# cs301_Group2_Sensing.net
KiCad netlist of a schematic drawn in Altium Designer
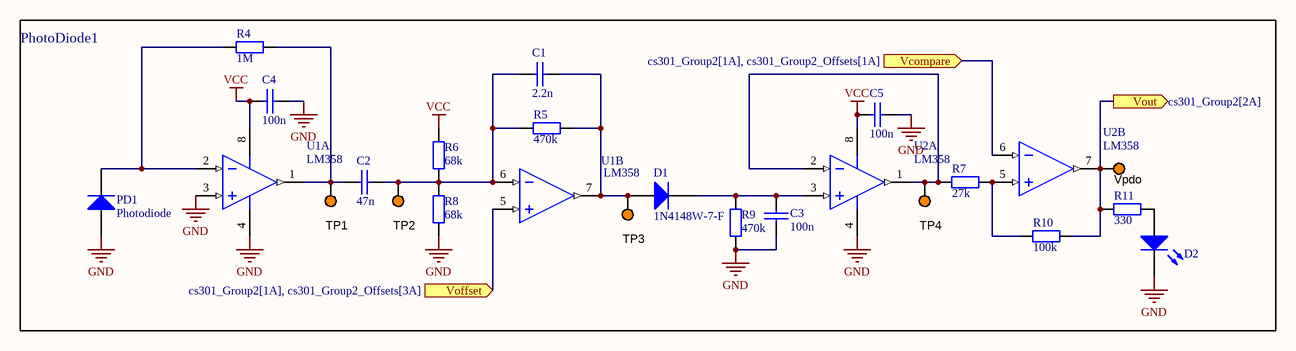
[diagram p0: cs301_Group2_Sensing.SchDoc]

(export (version "E")
  (design (tool "Eeschema 10.0.6"))
  (components
    (comp (ref "C1")
      (value "2.2n")
      (footprint "0805 CAP")
      (description "SMT ceramic capacitor 0805 size")
      (libsource (lib "EE209_Library") (part "CerCap_SMT_0805"))
    )
    (comp (ref "C2")
      (value "47n")
      (footprint "0805 CAP")
      (description "SMT ceramic capacitor 0805 size")
      (libsource (lib "EE209_Library") (part "CerCap_SMT_0805"))
    )
    (comp (ref "C3")
      (value "100n")
      (footprint "0805 CAP")
      (description "SMT ceramic capacitor 0805 size")
      (libsource (lib "EE209_Library") (part "CerCap_SMT_0805"))
    )
    (comp (ref "C4")
      (value "100n")
      (footprint "0805 CAP")
      (description "SMT ceramic capacitor 0805 size")
      (libsource (lib "EE209_Library") (part "CerCap_SMT_0805"))
    )
    (comp (ref "C5")
      (value "100n")
      (footprint "0805 CAP")
      (description "SMT ceramic capacitor 0805 size")
      (libsource (lib "EE209_Library") (part "CerCap_SMT_0805"))
    )
    (comp (ref "D1")
      (value "1N4148W-7-F")
      (footprint "SOD123")
      (description "1N4148 100V 200mA SOD-123 diode")
      (fields
        (field (name "MANUFACTURER") "ON Semiconductor")
        (field (name "MANUFACTURER PART NUMBER") "1N4148TR")
      )
      (libsource (lib "EE209_Library") (part "ES1H_SMT_DO214"))
    )
    (comp (ref "D2")
      (value "LTST-C170KGKT")
      (footprint "0805 LED")
      (description "SMT LED 0805 size")
      (fields (field (name "MANUFACTURER") "Lite-On Inc."))
      (libsource (lib "EE209_Library") (part "LED_SMT_0805"))
    )
    (comp (ref "PD1")
      (value "Photodiode")
      (footprint "SOD123")
      (description "DIODE GEN PURP 100V 300MA SOD123")
      (fields
        (field (name "MANUFACTURER") "Diodes Incorporated")
        (field (name "MANUFACTURER PART NUMBER") "1N4148W-13-F")
      )
      (libsource (lib "EE209_Library") (part "1N4148_SMT_SOD123"))
    )
    (comp (ref "R4")
      (value "1M")
      (footprint "0805 RES")
      (description "0805 resistor")
      (fields (field (name "PUBLISHER") "Altium Limited"))
      (libsource (lib "") (part "Res_SMT_0805_1"))
    )
    (comp (ref "R5")
      (value "470k")
      (footprint "0805 RES")
      (description "0805 resistor")
      (fields (field (name "PUBLISHER") "Altium Limited"))
      (libsource (lib "") (part "Res_SMT_0805_1"))
    )
    (comp (ref "R6")
      (value "68k")
      (footprint "0805 RES")
      (description "0805 resistor")
      (fields (field (name "PUBLISHER") "Altium Limited"))
      (libsource (lib "EE209_Library") (part "Res_SMT_0805"))
    )
    (comp (ref "R7")
      (value "27k")
      (footprint "0805 RES")
      (description "0805 resistor")
      (fields (field (name "PUBLISHER") "Altium Limited"))
      (libsource (lib "") (part "Res_SMT_0805_1"))
    )
    (comp (ref "R8")
      (value "68k")
      (footprint "0805 RES")
      (description "0805 resistor")
      (fields (field (name "PUBLISHER") "Altium Limited"))
      (libsource (lib "EE209_Library") (part "Res_SMT_0805"))
    )
    (comp (ref "R9")
      (value "470k")
      (footprint "0805 RES")
      (description "0805 resistor")
      (fields (field (name "PUBLISHER") "Altium Limited"))
      (libsource (lib "EE209_Library") (part "Res_SMT_0805"))
    )
    (comp (ref "R10")
      (value "100k")
      (footprint "0805 RES")
      (description "0805 resistor")
      (fields (field (name "PUBLISHER") "Altium Limited"))
      (libsource (lib "") (part "Res_SMT_0805_1"))
    )
    (comp (ref "R11")
      (value "330")
      (footprint "0805 RES")
      (description "0805 resistor")
      (fields (field (name "PUBLISHER") "Altium Limited"))
      (libsource (lib "") (part "Res_SMT_0805_2"))
    )
    (comp (ref "TP1")
      (value "5003")
      (footprint "TP_TH")
      (description "Test Point, Orange, 1-Pin THD, RoHS")
      (libsource (lib "EE209_Library") (part "TestPoint"))
    )
    (comp (ref "TP2")
      (value "5003")
      (footprint "TP_TH")
      (description "Test Point, Orange, 1-Pin THD, RoHS")
      (libsource (lib "EE209_Library") (part "TestPoint"))
    )
    (comp (ref "TP3")
      (value "5003")
      (footprint "TP_TH")
      (description "Test Point, Orange, 1-Pin THD, RoHS")
      (libsource (lib "EE209_Library") (part "TestPoint"))
    )
    (comp (ref "TP4")
      (value "5003")
      (footprint "TP_TH")
      (description "Test Point, Orange, 1-Pin THD, RoHS")
      (libsource (lib "EE209_Library") (part "TestPoint"))
    )
    (comp (ref "U1")
      (value "LM358")
      (footprint "SO - 8")
      (description "IC OPAMP 8SOIC")
      (libsource (lib "EE209_Library") (part "LM358_SMT_SOIC8"))
    )
    (comp (ref "U2")
      (value "LM358")
      (footprint "SO - 8")
      (description "IC OPAMP 8SOIC")
      (libsource (lib "EE209_Library") (part "LM358_SMT_SOIC8"))
    )
    (comp (ref "Vpdo")
      (value "5003")
      (footprint "TP_TH")
      (description "Test Point, Orange, 1-Pin THD, RoHS")
      (libsource (lib "EE209_Library") (part "TestPoint"))
    )
  )
  (nets
    (net (code "1") (name "/Vcompare") (class "Default")
      (node (ref "U2") (pin "6") (pinfunction "VINA-_6") (pintype "input"))
    )
    (net (code "2") (name "/Voffset") (class "Default")
      (node (ref "U1") (pin "5") (pinfunction "VINA+_5") (pintype "input"))
    )
    (net (code "3") (name "/Vout") (class "Default")
      (node (ref "R10") (pin "1") (pinfunction "1_1") (pintype "passive"))
      (node (ref "R11") (pin "1") (pinfunction "1_1") (pintype "passive"))
      (node (ref "U2") (pin "7") (pinfunction "VOUTA_7") (pintype "output"))
      (node (ref "Vpdo") (pin "1") (pinfunction "1_1") (pintype "passive"))
    )
    (net (code "4") (name "GND") (class "Default")
      (node (ref "C3") (pin "1") (pinfunction "1_1") (pintype "passive"))
      (node (ref "C4") (pin "2") (pinfunction "2_2") (pintype "passive"))
      (node (ref "C5") (pin "2") (pinfunction "2_2") (pintype "passive"))
      (node (ref "D2") (pin "2") (pinfunction "K_2") (pintype "passive"))
      (node (ref "PD1") (pin "1") (pinfunction "A_1") (pintype "passive"))
      (node (ref "R8") (pin "1") (pinfunction "1_1") (pintype "passive"))
      (node (ref "R9") (pin "1") (pinfunction "1_1") (pintype "passive"))
      (node (ref "U1") (pin "3") (pinfunction "VINA+_3") (pintype "input"))
      (node (ref "U1") (pin "4") (pinfunction "VSS_4") (pintype "power_in"))
      (node (ref "U2") (pin "4") (pinfunction "VSS_4") (pintype "power_in"))
    )
    (net (code "5") (name "Net-(D1-A)") (class "Default")
      (node (ref "C1") (pin "2") (pinfunction "2_2") (pintype "passive"))
      (node (ref "D1") (pin "1") (pinfunction "A_1") (pintype "passive"))
      (node (ref "R5") (pin "1") (pinfunction "1_1") (pintype "passive"))
      (node (ref "TP3") (pin "1") (pinfunction "1_1") (pintype "passive"))
      (node (ref "U1") (pin "7") (pinfunction "VOUTA_7") (pintype "output"))
    )
    (net (code "6") (name "Net-(D1-K)") (class "Default")
      (node (ref "C3") (pin "2") (pinfunction "2_2") (pintype "passive"))
      (node (ref "D1") (pin "2") (pinfunction "K_2") (pintype "passive"))
      (node (ref "R9") (pin "2") (pinfunction "2_2") (pintype "passive"))
      (node (ref "U2") (pin "3") (pinfunction "VINA+_3") (pintype "input"))
    )
    (net (code "7") (name "Net-(D2-A)") (class "Default")
      (node (ref "D2") (pin "1") (pinfunction "A_1") (pintype "passive"))
      (node (ref "R11") (pin "2") (pinfunction "2_2") (pintype "passive"))
    )
    (net (code "8") (name "Net-(PD1-K)") (class "Default")
      (node (ref "PD1") (pin "2") (pinfunction "K_2") (pintype "passive"))
      (node (ref "R4") (pin "2") (pinfunction "2_2") (pintype "passive"))
      (node (ref "U1") (pin "2") (pinfunction "VINA-_2") (pintype "input"))
    )
    (net (code "9") (name "Net-(U1A-VOUTA)") (class "Default")
      (node (ref "C2") (pin "1") (pinfunction "1_1") (pintype "passive"))
      (node (ref "R4") (pin "1") (pinfunction "1_1") (pintype "passive"))
      (node (ref "TP1") (pin "1") (pinfunction "1_1") (pintype "passive"))
      (node (ref "U1") (pin "1") (pinfunction "VOUTA_1") (pintype "output"))
    )
    (net (code "10") (name "Net-(U1B-VINA-)") (class "Default")
      (node (ref "C1") (pin "1") (pinfunction "1_1") (pintype "passive"))
      (node (ref "C2") (pin "2") (pinfunction "2_2") (pintype "passive"))
      (node (ref "R5") (pin "2") (pinfunction "2_2") (pintype "passive"))
      (node (ref "R6") (pin "1") (pinfunction "1_1") (pintype "passive"))
      (node (ref "R8") (pin "2") (pinfunction "2_2") (pintype "passive"))
      (node (ref "TP2") (pin "1") (pinfunction "1_1") (pintype "passive"))
      (node (ref "U1") (pin "6") (pinfunction "VINA-_6") (pintype "input"))
    )
    (net (code "11") (name "Net-(U2A-VINA-)") (class "Default")
      (node (ref "R7") (pin "2") (pinfunction "2_2") (pintype "passive"))
      (node (ref "TP4") (pin "1") (pinfunction "1_1") (pintype "passive"))
      (node (ref "U2") (pin "1") (pinfunction "VOUTA_1") (pintype "output"))
      (node (ref "U2") (pin "2") (pinfunction "VINA-_2") (pintype "input"))
    )
    (net (code "12") (name "Net-(U2B-VINA+)") (class "Default")
      (node (ref "R10") (pin "2") (pinfunction "2_2") (pintype "passive"))
      (node (ref "R7") (pin "1") (pinfunction "1_1") (pintype "passive"))
      (node (ref "U2") (pin "5") (pinfunction "VINA+_5") (pintype "input"))
    )
    (net (code "13") (name "VCC") (class "Default")
      (node (ref "C4") (pin "1") (pinfunction "1_1") (pintype "passive"))
      (node (ref "C5") (pin "1") (pinfunction "1_1") (pintype "passive"))
      (node (ref "R6") (pin "2") (pinfunction "2_2") (pintype "passive"))
      (node (ref "U1") (pin "8") (pinfunction "VDD_8") (pintype "power_in"))
      (node (ref "U2") (pin "8") (pinfunction "VDD_8") (pintype "power_in"))
    )
  )
)
